# Micro-Interactions.net
KiCad netlist of a schematic drawn in EAGLE
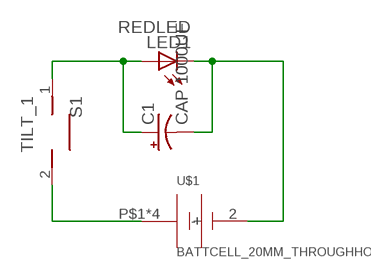
[diagram p0: schematic, sheet 1]

(export (version "E")
  (design (tool "Eeschema 10.0.6"))
  (components
    (comp (ref "C1")
      (value "CAP 1000UF")
      (footprint "eagle-import:CPOL-RADIAL-1000UF-25V")
      (libsource (lib "eagle-import") (part "CAP_POLPTH4"))
    )
    (comp (ref "LED1")
      (value "REDLED")
      (footprint "eagle-import:LED5MM")
      (libsource (lib "eagle-import") (part "LED5MM"))
    )
    (comp (ref "S1")
      (value "TILT_1")
      (footprint "eagle-import:DS-01")
      (libsource (lib "eagle-import") (part "DS01"))
    )
    (comp (ref "U$1")
      (value "BATTCELL_20MM_THROUGHHOLE")
      (footprint "eagle-import:BATTCON_20MM_4LEGS")
      (libsource (lib "eagle-import") (part "BATTCELL_20MM_THROUGHHOLE"))
    )
  )
  (nets
    (net (code "1") (name "Net-(C1-+)") (class "Default")
      (node (ref "C1") (pin "1") (pinfunction "+_1") (pintype "passive"))
      (node (ref "LED1") (pin "A") (pinfunction "A_A") (pintype "passive"))
      (node (ref "S1") (pin "1") (pinfunction "1_1") (pintype "passive"))
    )
    (net (code "2") (name "Net-(C1--)") (class "Default")
      (node (ref "C1") (pin "2") (pinfunction "-_2") (pintype "passive"))
      (node (ref "LED1") (pin "K") (pinfunction "C_K") (pintype "passive"))
      (node (ref "U$1") (pin "2") (pinfunction "-_2") (pintype "bidirectional"))
    )
    (net (code "3") (name "Net-(S1-Pad2)") (class "Default")
      (node (ref "S1") (pin "2") (pinfunction "2_2") (pintype "passive"))
      (node (ref "U$1") (pin "P$1") (pinfunction "+_P$1") (pintype "bidirectional"))
      (node (ref "U$1") (pin "P$2") (pinfunction "+_P$2") (pintype "bidirectional"))
      (node (ref "U$1") (pin "P$3") (pinfunction "+_P$3") (pintype "bidirectional"))
      (node (ref "U$1") (pin "P$4") (pinfunction "+_P$4") (pintype "bidirectional"))
    )
  )
)
